# SCH_bidouille_noel_2026-01-31.net
KiCad netlist of a schematic drawn in EasyEDA
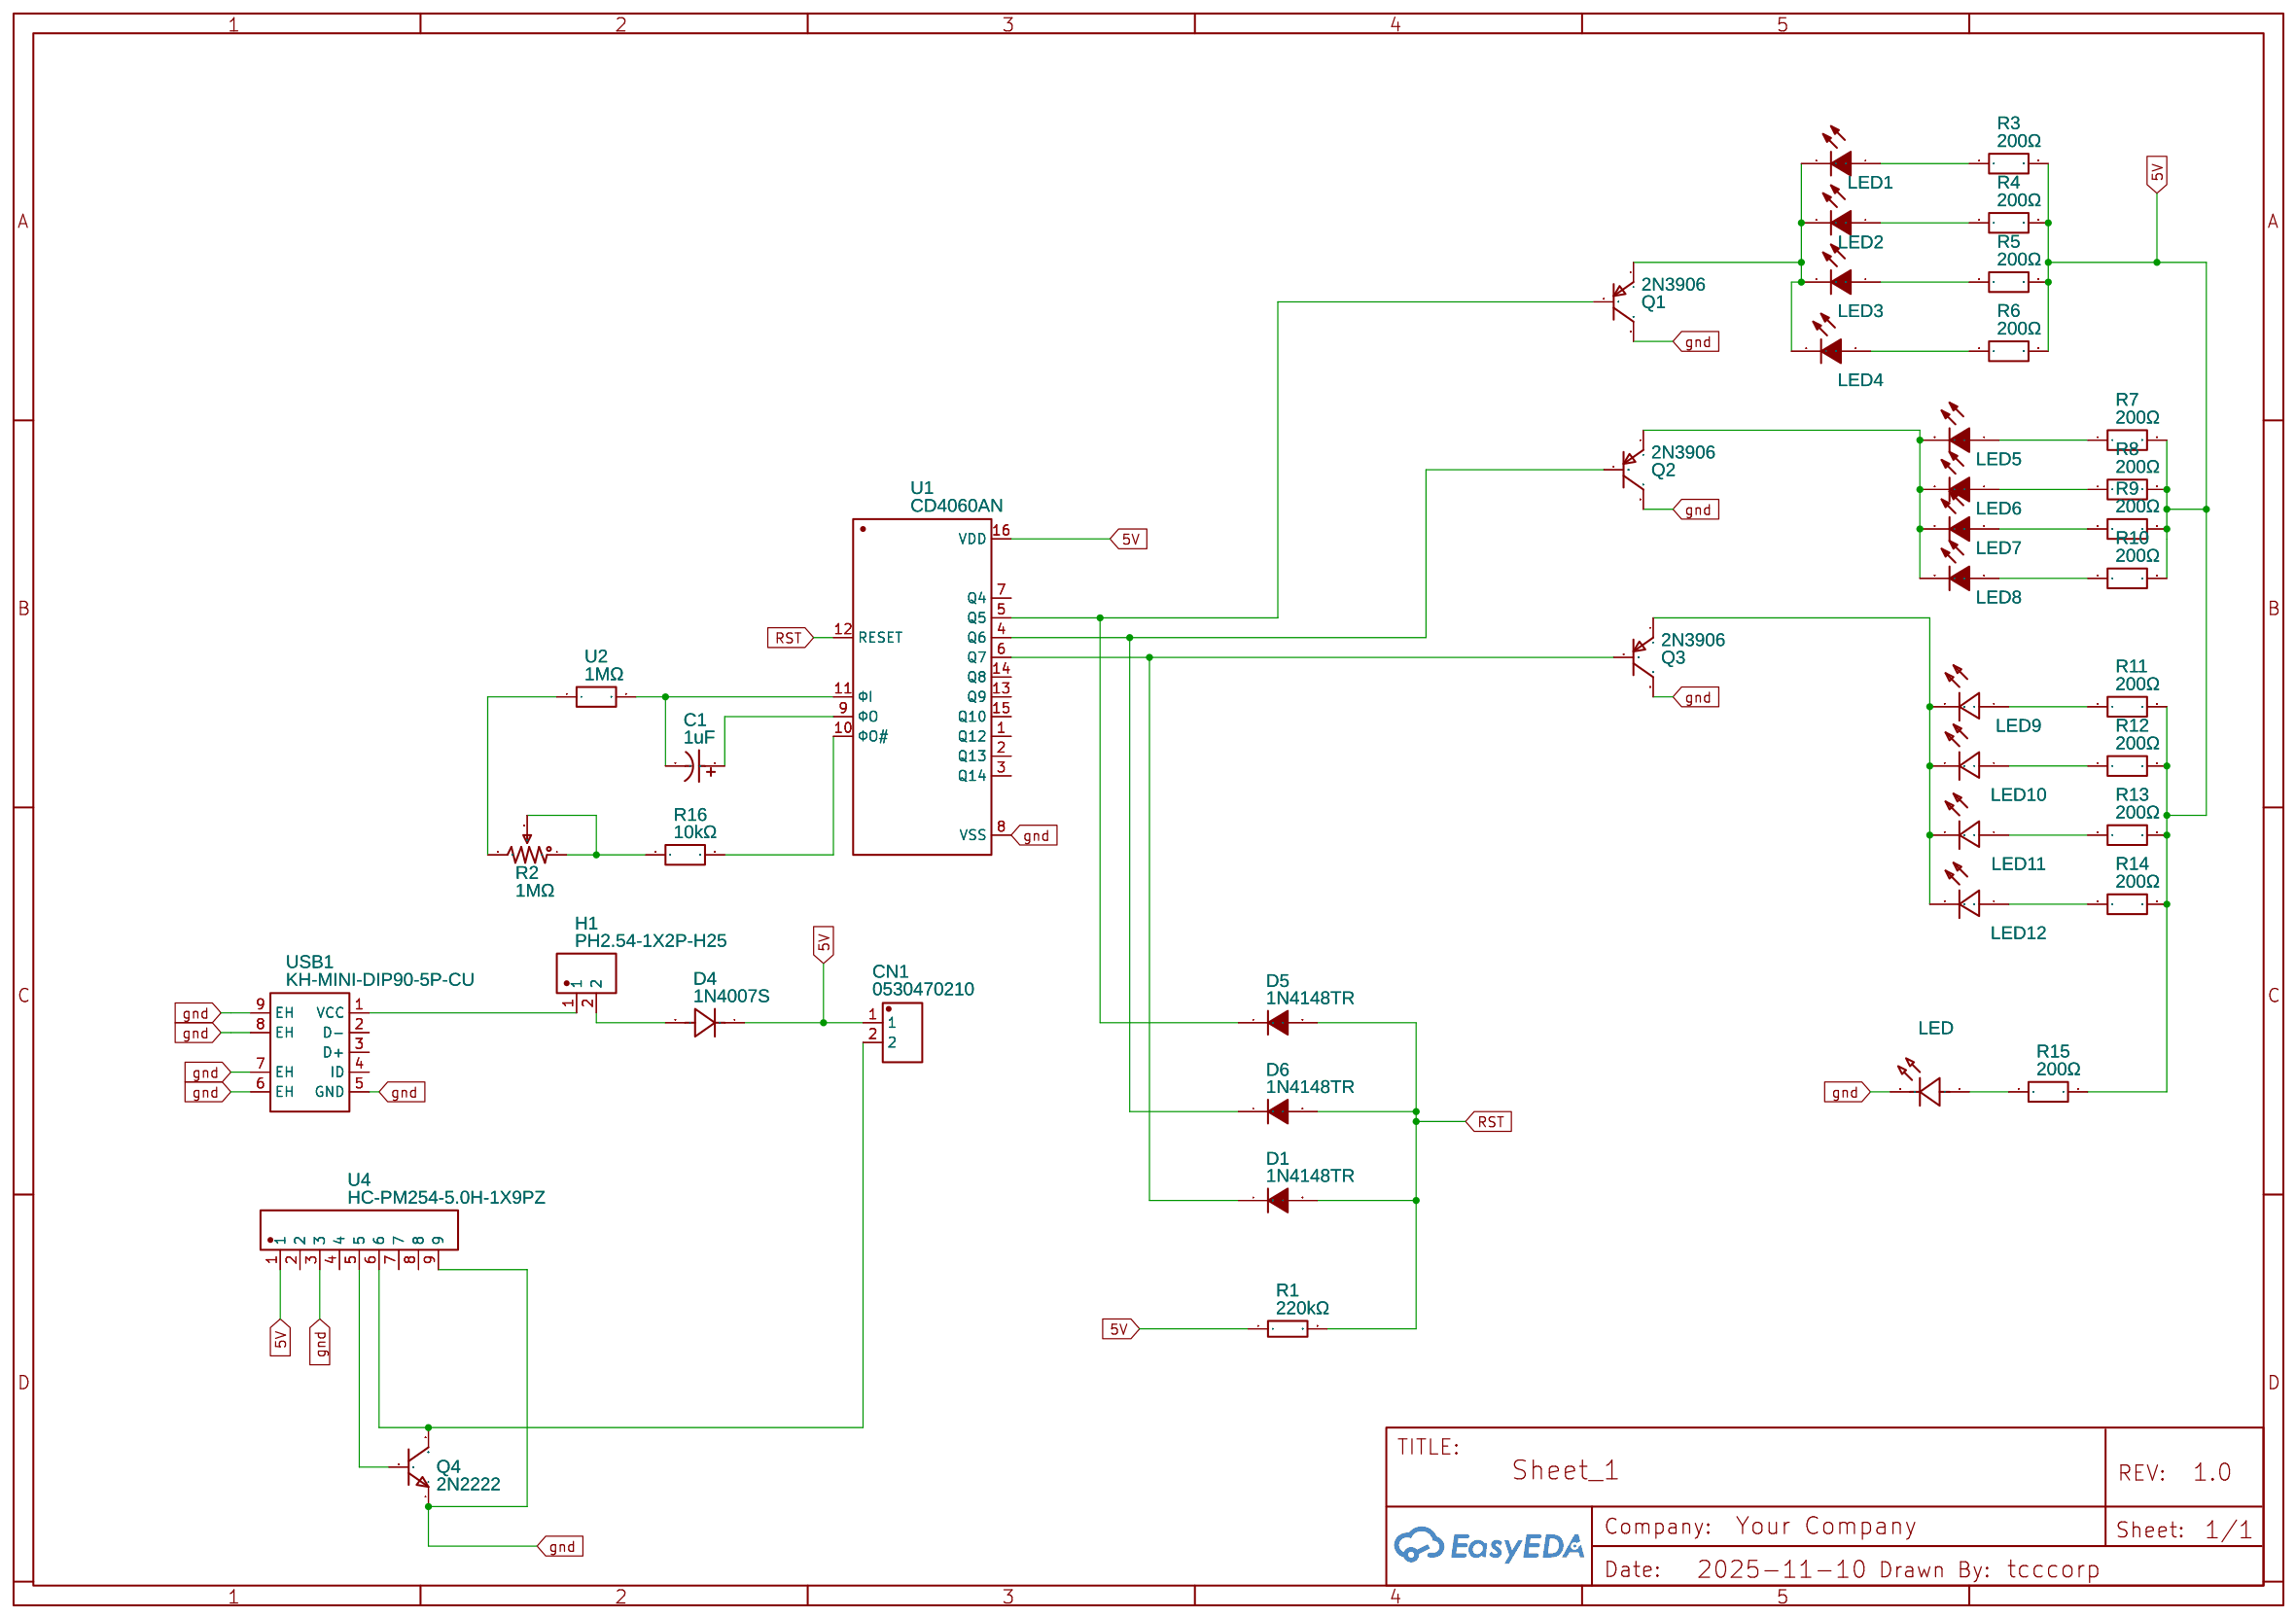
[diagram p0: schematic sheet]

(export (version "E")
  (design (tool "Eeschema 10.0.6"))
  (components
    (comp (ref "C1")
      (value "1uF")
      (fields
        (field (name "Manufacturer Part") "KM105M400E12RR0VH2FP0")
        (field (name "Manufacturer") "Chengx(承兴)")
      )
      (libsource (lib "") (part "1uF 400V 6.3*12"))
    )
    (comp (ref "CN1")
      (value "0530470210")
      (fields (field (name "Manufacturer Part") "530470210") (field (name "Manufacturer") "MOLEX"))
      (libsource (lib "") (part "0530470210"))
    )
    (comp (ref "D1")
      (value "1N4148TR")
      (fields (field (name "Manufacturer") "onsemi(安森美)"))
      (libsource (lib "") (part "1N4148TR"))
    )
    (comp (ref "D4")
      (value "1N4007S")
      (fields (field (name "Manufacturer") "星海"))
      (libsource (lib "") (part "1N4007S"))
    )
    (comp (ref "D5")
      (value "1N4148TR")
      (fields (field (name "Manufacturer") "onsemi(安森美)"))
      (libsource (lib "") (part "1N4148TR"))
    )
    (comp (ref "D6")
      (value "1N4148TR")
      (fields (field (name "Manufacturer") "onsemi(安森美)"))
      (libsource (lib "") (part "1N4148TR"))
    )
    (comp (ref "H1")
      (value "PH2.54-1X2P-H25")
      (fields (field (name "Manufacturer") "JXTCONN(聚兴泰)"))
      (libsource (lib "") (part "PH2.54-1X2P-H25"))
    )
    (comp (ref "LED")
      (value "TJ-L5FPTGCRMFCSFLC2R-A5")
      (fields (field (name "Manufacturer") "TOGIALED(统佳)"))
      (libsource (lib "") (part "TJ-L5FPTGCRMFCSFLC2R-A5"))
    )
    (comp (ref "LED1")
      (value "204-10SURD/S530-A3")
      (fields (field (name "Manufacturer") "EVERLIGHT(亿光)"))
      (libsource (lib "") (part "204-10SURD/S530-A3"))
    )
    (comp (ref "LED2")
      (value "204-10SURD/S530-A3")
      (fields (field (name "Manufacturer") "EVERLIGHT(亿光)"))
      (libsource (lib "") (part "204-10SURD/S530-A3"))
    )
    (comp (ref "LED3")
      (value "204-10SURD/S530-A3")
      (fields (field (name "Manufacturer") "EVERLIGHT(亿光)"))
      (libsource (lib "") (part "204-10SURD/S530-A3"))
    )
    (comp (ref "LED4")
      (value "204-10SURD/S530-A3")
      (fields (field (name "Manufacturer") "EVERLIGHT(亿光)"))
      (libsource (lib "") (part "204-10SURD/S530-A3"))
    )
    (comp (ref "LED5")
      (value "204-10SURD/S530-A3")
      (fields (field (name "Manufacturer") "EVERLIGHT(亿光)"))
      (libsource (lib "") (part "204-10SURD/S530-A3"))
    )
    (comp (ref "LED6")
      (value "204-10SURD/S530-A3")
      (fields (field (name "Manufacturer") "EVERLIGHT(亿光)"))
      (libsource (lib "") (part "204-10SURD/S530-A3"))
    )
    (comp (ref "LED7")
      (value "204-10SURD/S530-A3")
      (fields (field (name "Manufacturer") "EVERLIGHT(亿光)"))
      (libsource (lib "") (part "204-10SURD/S530-A3"))
    )
    (comp (ref "LED8")
      (value "204-10SURD/S530-A3")
      (fields (field (name "Manufacturer") "EVERLIGHT(亿光)"))
      (libsource (lib "") (part "204-10SURD/S530-A3"))
    )
    (comp (ref "LED9")
      (value "204-10UYT/S530-A3")
      (fields (field (name "Manufacturer") "EVERLIGHT(亿光)"))
      (libsource (lib "") (part "204-10UYT/S530-A3"))
    )
    (comp (ref "LED10")
      (value "204-10UYT/S530-A3")
      (fields (field (name "Manufacturer") "EVERLIGHT(亿光)"))
      (libsource (lib "") (part "204-10UYT/S530-A3"))
    )
    (comp (ref "LED11")
      (value "204-10UYT/S530-A3")
      (fields (field (name "Manufacturer") "EVERLIGHT(亿光)"))
      (libsource (lib "") (part "204-10UYT/S530-A3"))
    )
    (comp (ref "LED12")
      (value "204-10UYT/S530-A3")
      (fields (field (name "Manufacturer") "EVERLIGHT(亿光)"))
      (libsource (lib "") (part "204-10UYT/S530-A3"))
    )
    (comp (ref "Q1")
      (value "2N3906")
      (fields
        (field (name "Manufacturer Part") "2N3906(RANGE:200-300)")
        (field (name "Manufacturer") "CJ(江苏长电/长晶)")
      )
      (libsource (lib "") (part "2N3906"))
    )
    (comp (ref "Q2")
      (value "2N3906")
      (fields
        (field (name "Manufacturer Part") "2N3906(RANGE:200-300)")
        (field (name "Manufacturer") "CJ(江苏长电/长晶)")
      )
      (libsource (lib "") (part "2N3906"))
    )
    (comp (ref "Q3")
      (value "2N3906")
      (fields
        (field (name "Manufacturer Part") "2N3906(RANGE:200-300)")
        (field (name "Manufacturer") "CJ(江苏长电/长晶)")
      )
      (libsource (lib "") (part "2N3906"))
    )
    (comp (ref "Q4")
      (value "2N2222")
      (fields (field (name "Manufacturer Part") "2N2222A") (field (name "Manufacturer") "ST(先科)"))
      (libsource (lib "") (part "2N2222"))
    )
    (comp (ref "R1")
      (value "220kΩ")
      (fields
        (field (name "Manufacturer Part") "MFR0W4F2203A50")
        (field (name "Manufacturer") "UNI-ROYAL(厚声)")
      )
      (libsource (lib "") (part "MFR0W4F2203A50"))
    )
    (comp (ref "R2")
      (value "1MΩ")
      (fields (field (name "Manufacturer Part") "3296W-1-105") (field (name "Manufacturer") "JIERR(捷而瑞)"))
      (libsource (lib "") (part "3296W-1-105_C48997935"))
    )
    (comp (ref "R3")
      (value "200Ω")
      (fields (field (name "Manufacturer Part") "CR1/4W-200Ω±5%-ST52") (field (name "Manufacturer") "VO(翔胜)"))
      (libsource (lib "") (part "CR1/4W-200Ω±5%-ST52"))
    )
    (comp (ref "R4")
      (value "200Ω")
      (fields (field (name "Manufacturer Part") "CR1/4W-200Ω±5%-ST52") (field (name "Manufacturer") "VO(翔胜)"))
      (libsource (lib "") (part "CR1/4W-200Ω±5%-ST52"))
    )
    (comp (ref "R5")
      (value "200Ω")
      (fields (field (name "Manufacturer Part") "CR1/4W-200Ω±5%-ST52") (field (name "Manufacturer") "VO(翔胜)"))
      (libsource (lib "") (part "CR1/4W-200Ω±5%-ST52"))
    )
    (comp (ref "R6")
      (value "200Ω")
      (fields (field (name "Manufacturer Part") "CR1/4W-200Ω±5%-ST52") (field (name "Manufacturer") "VO(翔胜)"))
      (libsource (lib "") (part "CR1/4W-200Ω±5%-ST52"))
    )
    (comp (ref "R7")
      (value "200Ω")
      (fields (field (name "Manufacturer Part") "CR1/4W-200Ω±5%-ST52") (field (name "Manufacturer") "VO(翔胜)"))
      (libsource (lib "") (part "CR1/4W-200Ω±5%-ST52"))
    )
    (comp (ref "R8")
      (value "200Ω")
      (fields (field (name "Manufacturer Part") "CR1/4W-200Ω±5%-ST52") (field (name "Manufacturer") "VO(翔胜)"))
      (libsource (lib "") (part "CR1/4W-200Ω±5%-ST52"))
    )
    (comp (ref "R9")
      (value "200Ω")
      (fields (field (name "Manufacturer Part") "CR1/4W-200Ω±5%-ST52") (field (name "Manufacturer") "VO(翔胜)"))
      (libsource (lib "") (part "CR1/4W-200Ω±5%-ST52"))
    )
    (comp (ref "R10")
      (value "200Ω")
      (fields (field (name "Manufacturer Part") "CR1/4W-200Ω±5%-ST52") (field (name "Manufacturer") "VO(翔胜)"))
      (libsource (lib "") (part "CR1/4W-200Ω±5%-ST52"))
    )
    (comp (ref "R11")
      (value "200Ω")
      (fields (field (name "Manufacturer Part") "CR1/4W-200Ω±5%-ST52") (field (name "Manufacturer") "VO(翔胜)"))
      (libsource (lib "") (part "CR1/4W-200Ω±5%-ST52"))
    )
    (comp (ref "R12")
      (value "200Ω")
      (fields (field (name "Manufacturer Part") "CR1/4W-200Ω±5%-ST52") (field (name "Manufacturer") "VO(翔胜)"))
      (libsource (lib "") (part "CR1/4W-200Ω±5%-ST52"))
    )
    (comp (ref "R13")
      (value "200Ω")
      (fields (field (name "Manufacturer Part") "CR1/4W-200Ω±5%-ST52") (field (name "Manufacturer") "VO(翔胜)"))
      (libsource (lib "") (part "CR1/4W-200Ω±5%-ST52"))
    )
    (comp (ref "R14")
      (value "200Ω")
      (fields (field (name "Manufacturer Part") "CR1/4W-200Ω±5%-ST52") (field (name "Manufacturer") "VO(翔胜)"))
      (libsource (lib "") (part "CR1/4W-200Ω±5%-ST52"))
    )
    (comp (ref "R15")
      (value "200Ω")
      (fields (field (name "Manufacturer Part") "CR1/4W-200Ω±5%-ST52") (field (name "Manufacturer") "VO(翔胜)"))
      (libsource (lib "") (part "CR1/4W-200Ω±5%-ST52"))
    )
    (comp (ref "R16")
      (value "10kΩ")
      (fields
        (field (name "Manufacturer Part") "RN1/4W10KFT/BA1")
        (field (name "Manufacturer") "Tyohm(幸亚电阻)")
      )
      (libsource (lib "") (part "RN 1/4W 10K F T/B A1"))
    )
    (comp (ref "U1")
      (value "CD4060AN")
      (fields (field (name "Manufacturer") "HGSEMI(华冠)"))
      (libsource (lib "") (part "CD4060AN"))
    )
    (comp (ref "U2")
      (value "1MΩ")
      (fields (field (name "Manufacturer Part") "MF1/4W-1M±1%-OT52") (field (name "Manufacturer") "VO(翔胜)"))
      (libsource (lib "") (part "MF1/4W-1M±1%-OT52"))
    )
    (comp (ref "U4")
      (value "HC-PM254-5.0H-1X9PZ")
      (fields
        (field (name "Manufacturer Part") "HC-PM254-5.0H-1x9PZ")
        (field (name "Manufacturer") "HC(虹成电子)")
      )
      (libsource (lib "") (part "HC-PM254-5.0H-1X9PZ"))
    )
    (comp (ref "USB1")
      (value "KH-MINI-DIP90-5P-CU")
      (fields
        (field (name "Manufacturer Part") "KH-MINI-DIP90-5P-Cu")
        (field (name "Manufacturer") "kinghelm(金航标)")
      )
      (libsource (lib "") (part "KH-MINI-DIP90-5P-CU"))
    )
  )
  (nets
    (net (code "1") (name "5V") (class "Default")
      (node (ref "CN1") (pin "1") (pinfunction "1_1") (pintype "unspecified"))
      (node (ref "D4") (pin "1") (pinfunction "K_1") (pintype "unspecified"))
      (node (ref "R1") (pin "1") (pinfunction "1_1") (pintype "input"))
      (node (ref "R10") (pin "2") (pinfunction "2_2") (pintype "unspecified"))
      (node (ref "R11") (pin "2") (pinfunction "2_2") (pintype "unspecified"))
      (node (ref "R12") (pin "2") (pinfunction "2_2") (pintype "unspecified"))
      (node (ref "R13") (pin "2") (pinfunction "2_2") (pintype "unspecified"))
      (node (ref "R14") (pin "2") (pinfunction "2_2") (pintype "unspecified"))
      (node (ref "R15") (pin "2") (pinfunction "2_2") (pintype "unspecified"))
      (node (ref "R3") (pin "2") (pinfunction "2_2") (pintype "unspecified"))
      (node (ref "R4") (pin "2") (pinfunction "2_2") (pintype "unspecified"))
      (node (ref "R5") (pin "2") (pinfunction "2_2") (pintype "unspecified"))
      (node (ref "R6") (pin "2") (pinfunction "2_2") (pintype "unspecified"))
      (node (ref "R7") (pin "2") (pinfunction "2_2") (pintype "unspecified"))
      (node (ref "R8") (pin "2") (pinfunction "2_2") (pintype "unspecified"))
      (node (ref "R9") (pin "2") (pinfunction "2_2") (pintype "unspecified"))
      (node (ref "U1") (pin "16") (pinfunction "VDD_16") (pintype "unspecified"))
      (node (ref "U4") (pin "1") (pinfunction "1_1") (pintype "unspecified"))
    )
    (net (code "2") (name "Net-(D1-C)") (class "Default")
      (node (ref "D1") (pin "1") (pinfunction "C_1") (pintype "unspecified"))
      (node (ref "Q3") (pin "2") (pinfunction "B_2") (pintype "unspecified"))
      (node (ref "U1") (pin "6") (pinfunction "Q7_6") (pintype "unspecified"))
    )
    (net (code "3") (name "Net-(D4-A)") (class "Default")
      (node (ref "D4") (pin "2") (pinfunction "A_2") (pintype "unspecified"))
      (node (ref "H1") (pin "2") (pinfunction "2_2") (pintype "unspecified"))
    )
    (net (code "4") (name "Net-(D5-C)") (class "Default")
      (node (ref "D5") (pin "1") (pinfunction "C_1") (pintype "unspecified"))
      (node (ref "Q1") (pin "2") (pinfunction "B_2") (pintype "unspecified"))
      (node (ref "U1") (pin "5") (pinfunction "Q5_5") (pintype "unspecified"))
    )
    (net (code "5") (name "Net-(D6-C)") (class "Default")
      (node (ref "D6") (pin "1") (pinfunction "C_1") (pintype "unspecified"))
      (node (ref "Q2") (pin "2") (pinfunction "B_2") (pintype "unspecified"))
      (node (ref "U1") (pin "4") (pinfunction "Q6_4") (pintype "unspecified"))
    )
    (net (code "6") (name "Net-(LED-A)") (class "Default")
      (node (ref "LED") (pin "1") (pinfunction "A_1") (pintype "unspecified"))
      (node (ref "R15") (pin "1") (pinfunction "1_1") (pintype "unspecified"))
    )
    (net (code "7") (name "Net-(LED1-A)") (class "Default")
      (node (ref "LED1") (pin "1") (pinfunction "A_1") (pintype "input"))
      (node (ref "R3") (pin "1") (pinfunction "1_1") (pintype "unspecified"))
    )
    (net (code "8") (name "Net-(LED1-K)") (class "Default")
      (node (ref "LED1") (pin "2") (pinfunction "K_2") (pintype "input"))
      (node (ref "LED2") (pin "2") (pinfunction "K_2") (pintype "input"))
      (node (ref "LED3") (pin "2") (pinfunction "K_2") (pintype "input"))
      (node (ref "LED4") (pin "2") (pinfunction "K_2") (pintype "input"))
      (node (ref "Q1") (pin "1") (pinfunction "E_1") (pintype "unspecified"))
    )
    (net (code "9") (name "Net-(LED2-A)") (class "Default")
      (node (ref "LED2") (pin "1") (pinfunction "A_1") (pintype "input"))
      (node (ref "R4") (pin "1") (pinfunction "1_1") (pintype "unspecified"))
    )
    (net (code "10") (name "Net-(LED3-A)") (class "Default")
      (node (ref "LED3") (pin "1") (pinfunction "A_1") (pintype "input"))
      (node (ref "R5") (pin "1") (pinfunction "1_1") (pintype "unspecified"))
    )
    (net (code "11") (name "Net-(LED4-A)") (class "Default")
      (node (ref "LED4") (pin "1") (pinfunction "A_1") (pintype "input"))
      (node (ref "R6") (pin "1") (pinfunction "1_1") (pintype "unspecified"))
    )
    (net (code "12") (name "Net-(LED5-A)") (class "Default")
      (node (ref "LED5") (pin "1") (pinfunction "A_1") (pintype "input"))
      (node (ref "R7") (pin "1") (pinfunction "1_1") (pintype "unspecified"))
    )
    (net (code "13") (name "Net-(LED5-K)") (class "Default")
      (node (ref "LED5") (pin "2") (pinfunction "K_2") (pintype "input"))
      (node (ref "LED6") (pin "2") (pinfunction "K_2") (pintype "input"))
      (node (ref "LED7") (pin "2") (pinfunction "K_2") (pintype "input"))
      (node (ref "LED8") (pin "2") (pinfunction "K_2") (pintype "input"))
      (node (ref "Q2") (pin "1") (pinfunction "E_1") (pintype "unspecified"))
    )
    (net (code "14") (name "Net-(LED6-A)") (class "Default")
      (node (ref "LED6") (pin "1") (pinfunction "A_1") (pintype "input"))
      (node (ref "R8") (pin "1") (pinfunction "1_1") (pintype "unspecified"))
    )
    (net (code "15") (name "Net-(LED7-A)") (class "Default")
      (node (ref "LED7") (pin "1") (pinfunction "A_1") (pintype "input"))
      (node (ref "R9") (pin "1") (pinfunction "1_1") (pintype "unspecified"))
    )
    (net (code "16") (name "Net-(LED8-A)") (class "Default")
      (node (ref "LED8") (pin "1") (pinfunction "A_1") (pintype "input"))
      (node (ref "R10") (pin "1") (pinfunction "1_1") (pintype "unspecified"))
    )
    (net (code "17") (name "Net-(LED9-Pad1)") (class "Default")
      (node (ref "LED9") (pin "1") (pinfunction "1_1") (pintype "unspecified"))
      (node (ref "R11") (pin "1") (pinfunction "1_1") (pintype "unspecified"))
    )
    (net (code "18") (name "Net-(LED10-Pad1)") (class "Default")
      (node (ref "LED10") (pin "1") (pinfunction "1_1") (pintype "unspecified"))
      (node (ref "R12") (pin "1") (pinfunction "1_1") (pintype "unspecified"))
    )
    (net (code "19") (name "Net-(LED11-Pad1)") (class "Default")
      (node (ref "LED11") (pin "1") (pinfunction "1_1") (pintype "unspecified"))
      (node (ref "R13") (pin "1") (pinfunction "1_1") (pintype "unspecified"))
    )
    (net (code "20") (name "Net-(LED12-Pad1)") (class "Default")
      (node (ref "LED12") (pin "1") (pinfunction "1_1") (pintype "unspecified"))
      (node (ref "R14") (pin "1") (pinfunction "1_1") (pintype "unspecified"))
    )
    (net (code "21") (name "Net-(Q3-E)") (class "Default")
      (node (ref "LED10") (pin "2") (pinfunction "2_2") (pintype "unspecified"))
      (node (ref "LED11") (pin "2") (pinfunction "2_2") (pintype "unspecified"))
      (node (ref "LED12") (pin "2") (pinfunction "2_2") (pintype "unspecified"))
      (node (ref "LED9") (pin "2") (pinfunction "2_2") (pintype "unspecified"))
      (node (ref "Q3") (pin "1") (pinfunction "E_1") (pintype "unspecified"))
    )
    (net (code "22") (name "Net-(Q4-B)") (class "Default")
      (node (ref "Q4") (pin "2") (pinfunction "B_2") (pintype "unspecified"))
      (node (ref "U4") (pin "5") (pinfunction "5_5") (pintype "unspecified"))
    )
    (net (code "23") (name "Net-(Q4-C)") (class "Default")
      (node (ref "CN1") (pin "2") (pinfunction "2_2") (pintype "unspecified"))
      (node (ref "Q4") (pin "3") (pinfunction "C_3") (pintype "unspecified"))
      (node (ref "U4") (pin "6") (pinfunction "6_6") (pintype "unspecified"))
    )
    (net (code "24") (name "Net-(R2-Pad3)") (class "Default")
      (node (ref "R2") (pin "3") (pinfunction "3_3") (pintype "unspecified"))
      (node (ref "U2") (pin "1") (pinfunction "1_1") (pintype "unspecified"))
    )
    (net (code "25") (name "Net-(R16-Pad1)") (class "Default")
      (node (ref "R16") (pin "1") (pinfunction "1_1") (pintype "unspecified"))
      (node (ref "R2") (pin "1") (pinfunction "1_1") (pintype "unspecified"))
      (node (ref "R2") (pin "2") (pinfunction "2_2") (pintype "unspecified"))
    )
    (net (code "26") (name "Net-(U1-ФI)") (class "Default")
      (node (ref "C1") (pin "2") (pinfunction "2_2") (pintype "input"))
      (node (ref "U1") (pin "11") (pinfunction "ФI_11") (pintype "unspecified"))
      (node (ref "U2") (pin "2") (pinfunction "2_2") (pintype "unspecified"))
    )
    (net (code "27") (name "Net-(U1-ФO#)") (class "Default")
      (node (ref "R16") (pin "2") (pinfunction "2_2") (pintype "unspecified"))
      (node (ref "U1") (pin "10") (pinfunction "ФO#_10") (pintype "unspecified"))
    )
    (net (code "28") (name "Net-(U1-ФO)") (class "Default")
      (node (ref "C1") (pin "1") (pinfunction "1_1") (pintype "input"))
      (node (ref "U1") (pin "9") (pinfunction "ФO_9") (pintype "unspecified"))
    )
    (net (code "29") (name "Net-(USB1-VCC)") (class "Default")
      (node (ref "H1") (pin "1") (pinfunction "1_1") (pintype "unspecified"))
      (node (ref "USB1") (pin "1") (pinfunction "VCC_1") (pintype "input"))
    )
    (net (code "30") (name "RST") (class "Default")
      (node (ref "D1") (pin "2") (pinfunction "A_2") (pintype "unspecified"))
      (node (ref "D5") (pin "2") (pinfunction "A_2") (pintype "unspecified"))
      (node (ref "D6") (pin "2") (pinfunction "A_2") (pintype "unspecified"))
      (node (ref "R1") (pin "2") (pinfunction "2_2") (pintype "input"))
      (node (ref "U1") (pin "12") (pinfunction "RESET_12") (pintype "unspecified"))
    )
    (net (code "31") (name "gnd") (class "Default")
      (node (ref "LED") (pin "2") (pinfunction "K_2") (pintype "unspecified"))
      (node (ref "Q1") (pin "3") (pinfunction "C_3") (pintype "unspecified"))
      (node (ref "Q2") (pin "3") (pinfunction "C_3") (pintype "unspecified"))
      (node (ref "Q3") (pin "3") (pinfunction "C_3") (pintype "unspecified"))
      (node (ref "Q4") (pin "1") (pinfunction "E_1") (pintype "unspecified"))
      (node (ref "U1") (pin "8") (pinfunction "VSS_8") (pintype "unspecified"))
      (node (ref "U4") (pin "3") (pinfunction "3_3") (pintype "unspecified"))
      (node (ref "U4") (pin "9") (pinfunction "9_9") (pintype "unspecified"))
      (node (ref "USB1") (pin "5") (pinfunction "GND_5") (pintype "input"))
      (node (ref "USB1") (pin "6") (pinfunction "EH_6") (pintype "unspecified"))
      (node (ref "USB1") (pin "7") (pinfunction "EH_7") (pintype "unspecified"))
      (node (ref "USB1") (pin "8") (pinfunction "EH_8") (pintype "unspecified"))
      (node (ref "USB1") (pin "9") (pinfunction "EH_9") (pintype "unspecified"))
    )
    (net (code "32") (name "unconnected-(U1-Q4-Pad7)") (class "Default")
      (node (ref "U1") (pin "7") (pinfunction "Q4_7") (pintype "unspecified"))
    )
    (net (code "33") (name "unconnected-(U1-Q8-Pad14)") (class "Default")
      (node (ref "U1") (pin "14") (pinfunction "Q8_14") (pintype "unspecified"))
    )
    (net (code "34") (name "unconnected-(U1-Q9-Pad13)") (class "Default")
      (node (ref "U1") (pin "13") (pinfunction "Q9_13") (pintype "unspecified"))
    )
    (net (code "35") (name "unconnected-(U1-Q10-Pad15)") (class "Default")
      (node (ref "U1") (pin "15") (pinfunction "Q10_15") (pintype "unspecified"))
    )
    (net (code "36") (name "unconnected-(U1-Q12-Pad1)") (class "Default")
      (node (ref "U1") (pin "1") (pinfunction "Q12_1") (pintype "unspecified"))
    )
    (net (code "37") (name "unconnected-(U1-Q13-Pad2)") (class "Default")
      (node (ref "U1") (pin "2") (pinfunction "Q13_2") (pintype "unspecified"))
    )
    (net (code "38") (name "unconnected-(U1-Q14-Pad3)") (class "Default")
      (node (ref "U1") (pin "3") (pinfunction "Q14_3") (pintype "unspecified"))
    )
    (net (code "39") (name "unconnected-(U4-Pad2)") (class "Default")
      (node (ref "U4") (pin "2") (pinfunction "2_2") (pintype "unspecified"))
    )
    (net (code "40") (name "unconnected-(U4-Pad4)") (class "Default")
      (node (ref "U4") (pin "4") (pinfunction "4_4") (pintype "unspecified"))
    )
    (net (code "41") (name "unconnected-(U4-Pad7)") (class "Default")
      (node (ref "U4") (pin "7") (pinfunction "7_7") (pintype "unspecified"))
    )
    (net (code "42") (name "unconnected-(U4-Pad8)") (class "Default")
      (node (ref "U4") (pin "8") (pinfunction "8_8") (pintype "unspecified"))
    )
    (net (code "43") (name "unconnected-(USB1-D+-Pad3)") (class "Default")
      (node (ref "USB1") (pin "3") (pinfunction "D+_3") (pintype "input"))
    )
    (net (code "44") (name "unconnected-(USB1-D--Pad2)") (class "Default")
      (node (ref "USB1") (pin "2") (pinfunction "D-_2") (pintype "input"))
    )
    (net (code "45") (name "unconnected-(USB1-ID-Pad4)") (class "Default")
      (node (ref "USB1") (pin "4") (pinfunction "ID_4") (pintype "input"))
    )
  )
)
